# PWR_PoE_PD_1000BASE-T.net
KiCad netlist of a schematic drawn in Altium Designer
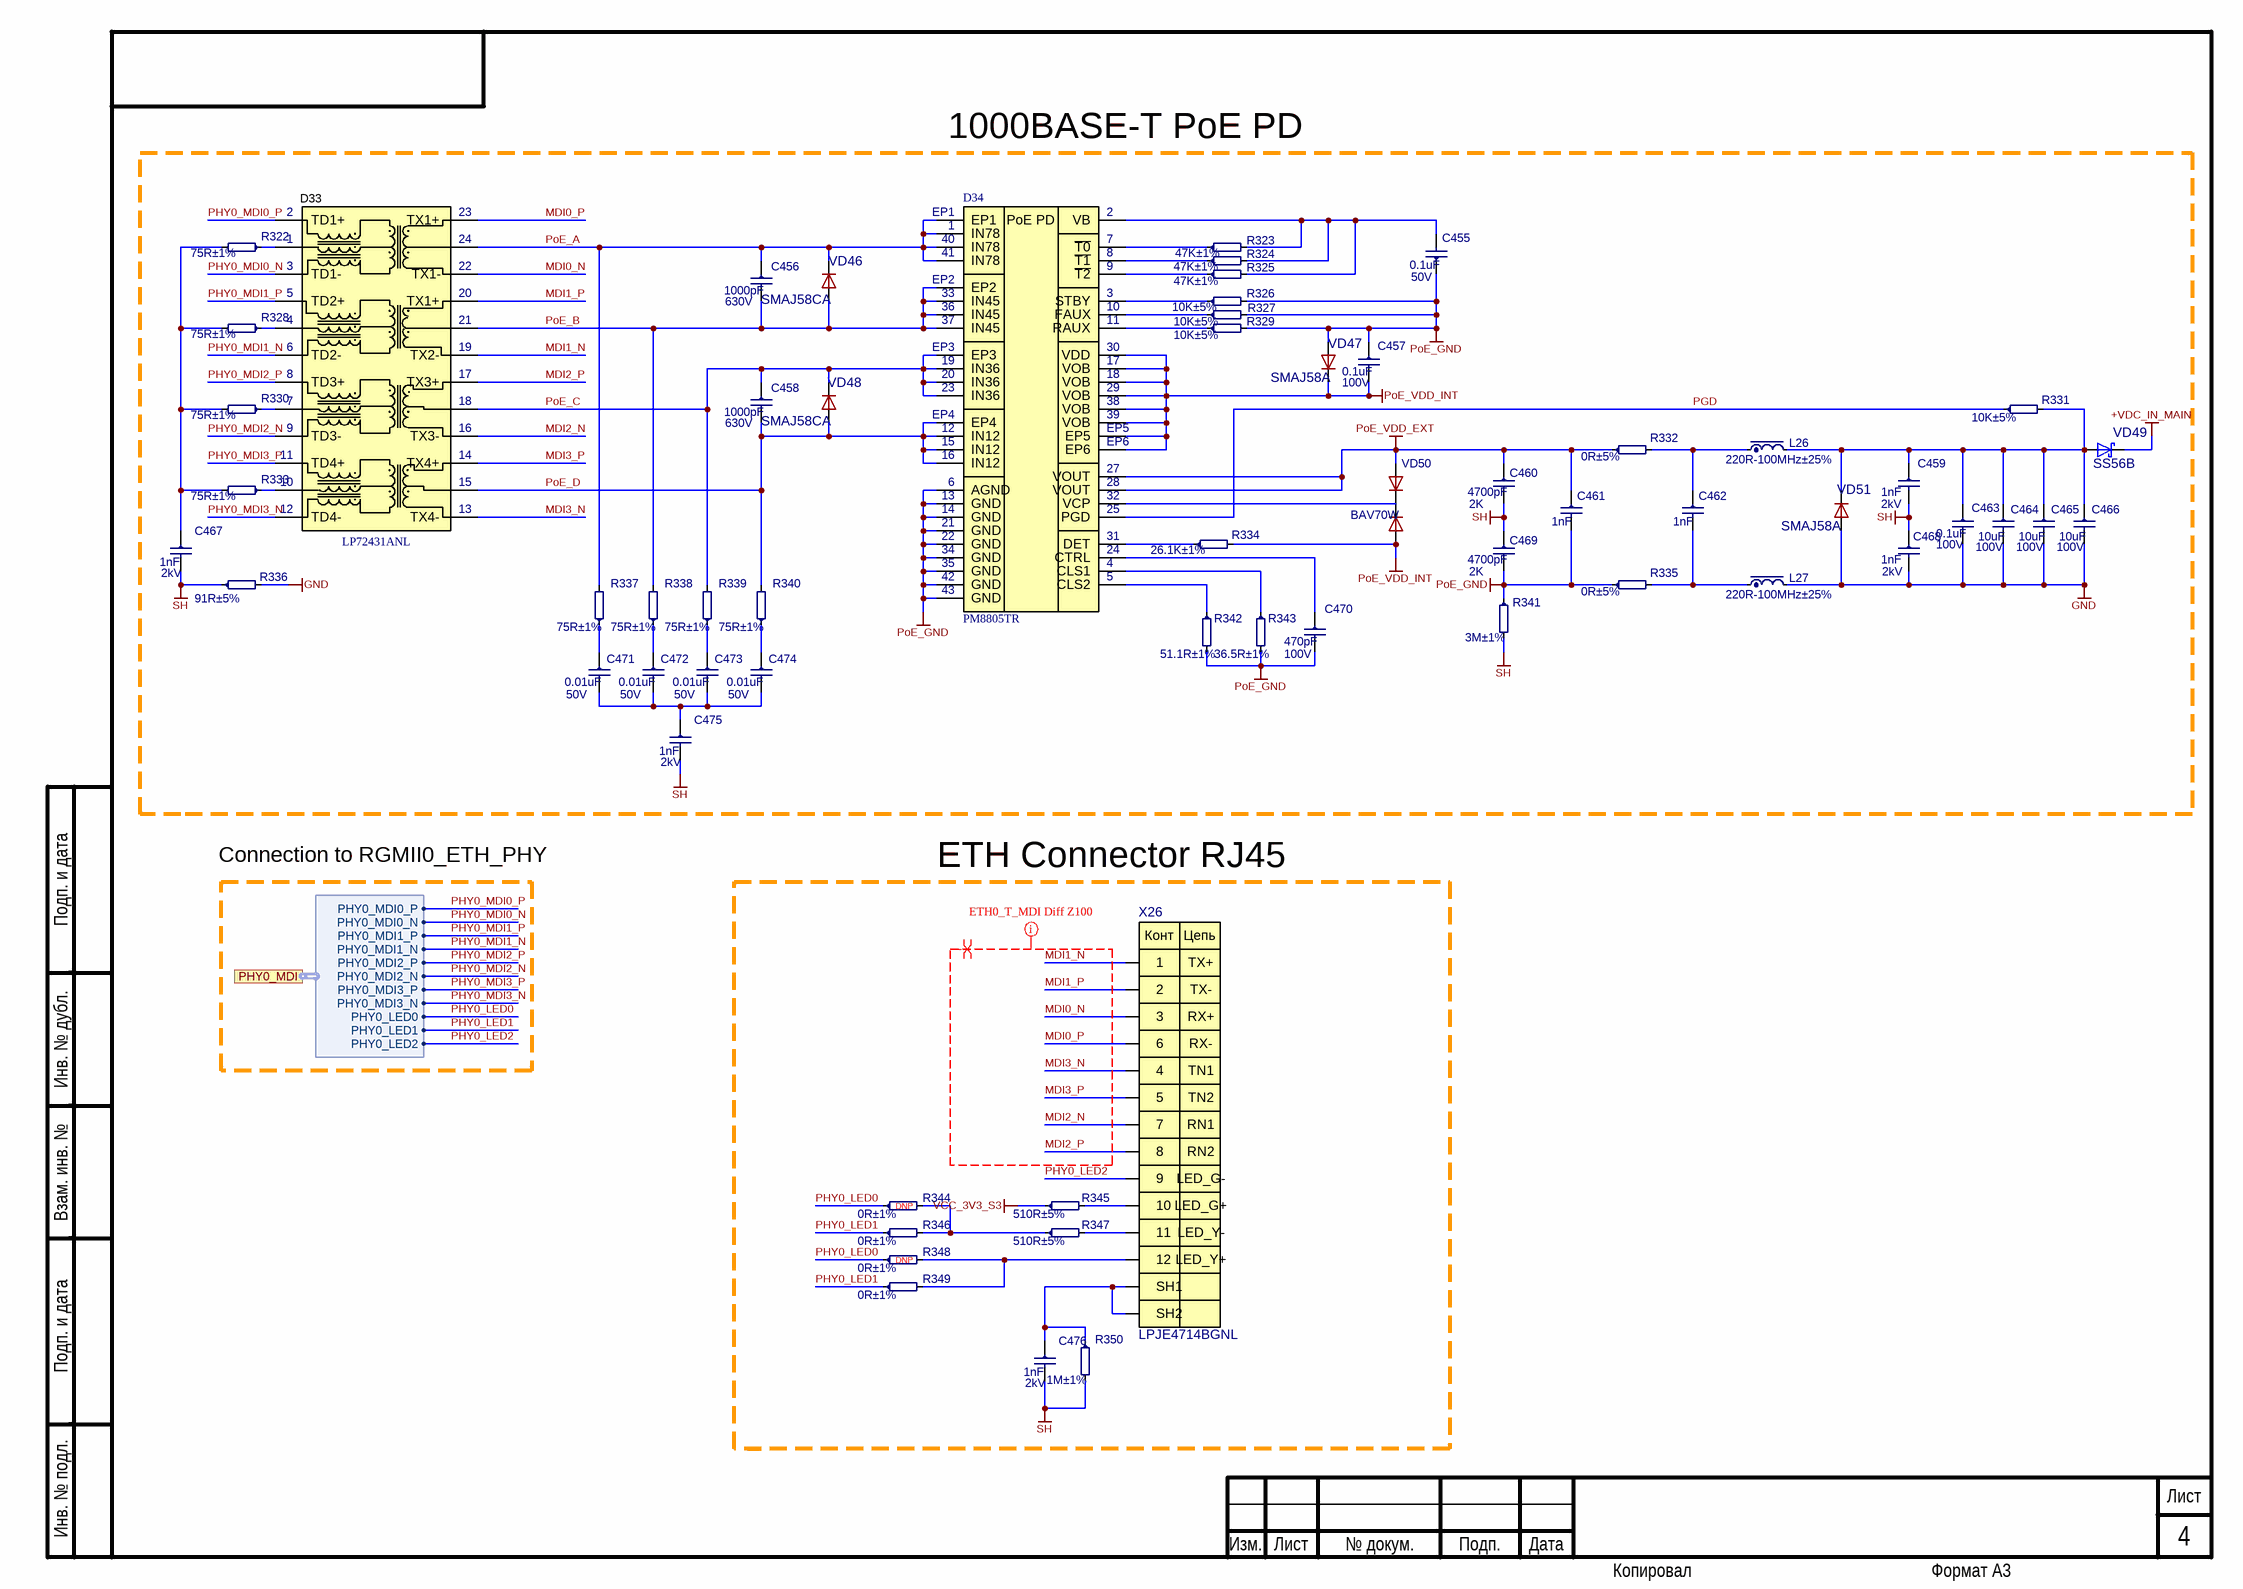
[diagram p0: PWR_PoE_PD_1000BASE-T.SchDoc]

(export (version "E")
  (design (tool "Eeschema 10.0.6"))
  (components
    (comp (ref "C455")
      (value "0.1uF")
      (footprint "C0603")
      (fields
        (field (name "VOLTAGE") "50V")
        (field (name "PART NUMBER") "0603-X7R-50V-0.1uF±10%")
        (field (name "TOLERANCE") "10%")
        (field (name "MANUFACTURER") "Yageo")
      )
      (libsource (lib "ATB") (part "C"))
    )
    (comp (ref "C456")
      (value "1000pF")
      (footprint "C1206")
      (fields
        (field (name "VOLTAGE") "630V")
        (field (name "PART NUMBER") "1206-NP0-630V-1000pF±5%")
        (field (name "TOLERANCE") "5%")
        (field (name "MANUFACTURER") "Yageo")
      )
      (libsource (lib "ATB") (part "C"))
    )
    (comp (ref "C457")
      (value "0.1uF")
      (footprint "C1206")
      (fields
        (field (name "VOLTAGE") "100V")
        (field (name "PART NUMBER") "1206-X7R-100V-0.1uF±10%")
        (field (name "TOLERANCE") "10%")
        (field (name "MANUFACTURER") "KEMET")
      )
      (libsource (lib "ATB") (part "C"))
    )
    (comp (ref "C458")
      (value "1000pF")
      (footprint "C1206")
      (fields
        (field (name "VOLTAGE") "630V")
        (field (name "PART NUMBER") "1206-NP0-630V-1000pF±5%")
        (field (name "TOLERANCE") "5%")
        (field (name "MANUFACTURER") "Yageo")
      )
      (libsource (lib "ATB") (part "C"))
    )
    (comp (ref "C459")
      (value "1nF")
      (footprint "C1812")
      (fields
        (field (name "VOLTAGE") "2kV")
        (field (name "PART NUMBER") "1812-C0G-2kV-1nF±10%")
        (field (name "TOLERANCE") "5%")
        (field (name "MANUFACTURER") "FH")
      )
      (libsource (lib "ATB") (part "C"))
    )
    (comp (ref "C460")
      (value "4700pF")
      (footprint "C1206")
      (fields
        (field (name "VOLTAGE") "2K")
        (field (name "PART NUMBER") "1206-X7R-2K-4700pF±10%")
        (field (name "TOLERANCE") "10%")
        (field (name "MANUFACTURER") "FH")
      )
      (libsource (lib "ATB") (part "C"))
    )
    (comp (ref "C461")
      (value "1nF")
      (footprint "C1206")
      (description "Ceramic Capacitor 1206 1nF ±10% 2kV X7R")
      (fields (field (name "VOLTAGE") "2kV") (field (name "PART NUMBER") "1206-X7R-2K-1000pF±10%"))
      (libsource (lib "ATB") (part "C"))
    )
    (comp (ref "C462")
      (value "1nF")
      (footprint "C1206")
      (description "Ceramic Capacitor 1206 1nF ±10% 2kV X7R")
      (fields (field (name "VOLTAGE") "2kV") (field (name "PART NUMBER") "1206-X7R-2K-1000pF±10%"))
      (libsource (lib "ATB") (part "C"))
    )
    (comp (ref "C463")
      (value "0.1uF")
      (footprint "C1206")
      (fields
        (field (name "VOLTAGE") "100V")
        (field (name "PART NUMBER") "1206-X7R-100V-0.1uF±10%")
        (field (name "TOLERANCE") "10%")
        (field (name "MANUFACTURER") "KEMET")
      )
      (libsource (lib "ATB") (part "C"))
    )
    (comp (ref "C464")
      (value "10uF")
      (footprint "C1210")
      (fields
        (field (name "VOLTAGE") "100V")
        (field (name "PART NUMBER") "1210-X7S-100V-10uF±10%")
        (field (name "TOLERANCE") "10%")
        (field (name "MANUFACTURER") "Samsung Electro-Mechanics")
      )
      (libsource (lib "ATB") (part "C"))
    )
    (comp (ref "C465")
      (value "10uF")
      (footprint "C1210")
      (fields
        (field (name "VOLTAGE") "100V")
        (field (name "PART NUMBER") "1210-X7S-100V-10uF±10%")
        (field (name "TOLERANCE") "10%")
        (field (name "MANUFACTURER") "Samsung Electro-Mechanics")
      )
      (libsource (lib "ATB") (part "C"))
    )
    (comp (ref "C466")
      (value "10uF")
      (footprint "C1210")
      (fields
        (field (name "VOLTAGE") "100V")
        (field (name "PART NUMBER") "1210-X7S-100V-10uF±10%")
        (field (name "TOLERANCE") "10%")
        (field (name "MANUFACTURER") "Samsung Electro-Mechanics")
      )
      (libsource (lib "ATB") (part "C"))
    )
    (comp (ref "C467")
      (value "1nF")
      (footprint "C1812")
      (fields
        (field (name "VOLTAGE") "2kV")
        (field (name "PART NUMBER") "1812-C0G-2kV-1nF±10%")
        (field (name "TOLERANCE") "5%")
        (field (name "MANUFACTURER") "FH")
      )
      (libsource (lib "ATB") (part "C"))
    )
    (comp (ref "C468")
      (value "1nF")
      (footprint "C1812")
      (fields
        (field (name "VOLTAGE") "2kV")
        (field (name "PART NUMBER") "1812-C0G-2kV-1nF±10%")
        (field (name "TOLERANCE") "5%")
        (field (name "MANUFACTURER") "FH")
      )
      (libsource (lib "ATB") (part "C"))
    )
    (comp (ref "C469")
      (value "4700pF")
      (footprint "C1206")
      (fields
        (field (name "VOLTAGE") "2K")
        (field (name "PART NUMBER") "1206-X7R-2K-4700pF±10%")
        (field (name "TOLERANCE") "10%")
        (field (name "MANUFACTURER") "FH")
      )
      (libsource (lib "ATB") (part "C"))
    )
    (comp (ref "C470")
      (value "470pF")
      (footprint "C0805")
      (fields
        (field (name "VOLTAGE") "100V")
        (field (name "PART NUMBER") "0805-X7R-100V-470pF±10%")
        (field (name "TOLERANCE") "10%")
        (field (name "MANUFACTURER") "Yageo")
      )
      (libsource (lib "ATB") (part "C"))
    )
    (comp (ref "C471")
      (value "0.01uF")
      (footprint "C0603")
      (fields
        (field (name "VOLTAGE") "50V")
        (field (name "PART NUMBER") "0603-X7R-50V-0.01uF±10%")
        (field (name "TOLERANCE") "10%")
        (field (name "MANUFACTURER") "Yageo")
      )
      (libsource (lib "ATB") (part "C"))
    )
    (comp (ref "C472")
      (value "0.01uF")
      (footprint "C0603")
      (fields
        (field (name "VOLTAGE") "50V")
        (field (name "PART NUMBER") "0603-X7R-50V-0.01uF±10%")
        (field (name "TOLERANCE") "10%")
        (field (name "MANUFACTURER") "Yageo")
      )
      (libsource (lib "ATB") (part "C"))
    )
    (comp (ref "C473")
      (value "0.01uF")
      (footprint "C0603")
      (fields
        (field (name "VOLTAGE") "50V")
        (field (name "PART NUMBER") "0603-X7R-50V-0.01uF±10%")
        (field (name "TOLERANCE") "10%")
        (field (name "MANUFACTURER") "Yageo")
      )
      (libsource (lib "ATB") (part "C"))
    )
    (comp (ref "C474")
      (value "0.01uF")
      (footprint "C0603")
      (fields
        (field (name "VOLTAGE") "50V")
        (field (name "PART NUMBER") "0603-X7R-50V-0.01uF±10%")
        (field (name "TOLERANCE") "10%")
        (field (name "MANUFACTURER") "Yageo")
      )
      (libsource (lib "ATB") (part "C"))
    )
    (comp (ref "C475")
      (value "1nF")
      (footprint "C1812")
      (fields
        (field (name "VOLTAGE") "2kV")
        (field (name "PART NUMBER") "1812-C0G-2kV-1nF±10%")
        (field (name "TOLERANCE") "5%")
        (field (name "MANUFACTURER") "FH")
      )
      (libsource (lib "ATB") (part "C"))
    )
    (comp (ref "C476")
      (value "1nF")
      (footprint "C1812")
      (fields
        (field (name "VOLTAGE") "2kV")
        (field (name "PART NUMBER") "1812-C0G-2kV-1nF±10%")
        (field (name "TOLERANCE") "5%")
        (field (name "MANUFACTURER") "FH")
      )
      (libsource (lib "ATB") (part "C"))
    )
    (comp (ref "D33")
      (value "LP72431ANL")
      (footprint "LP72431ANL")
      (fields (field (name "MANUFACTURER") "LINK-PP"))
      (libsource (lib "LIB_RK") (part "LP72431ANL"))
    )
    (comp (ref "D34")
      (value "PM8805TR")
      (footprint "PM8805TR")
      (fields (field (name "MANUFACTURER") "ST"))
      (libsource (lib "LIB_RK") (part "PM8805TR"))
    )
    (comp (ref "L26")
      (value "220R-100MHz±25%")
      (footprint "L0805")
      (fields
        (field (name "PART NUMBER") "0805-3A-220R-100MHz")
        (field (name "TOLERANCE") "25%")
        (field (name "MANUFACTURER") "TDK")
      )
      (libsource (lib "ATB") (part "L"))
    )
    (comp (ref "L27")
      (value "220R-100MHz±25%")
      (footprint "L0805")
      (fields
        (field (name "PART NUMBER") "0805-3A-220R-100MHz")
        (field (name "TOLERANCE") "25%")
        (field (name "MANUFACTURER") "TDK")
      )
      (libsource (lib "ATB") (part "L"))
    )
    (comp (ref "R322")
      (value "75R±1%")
      (footprint "R0603")
      (fields
        (field (name "PART NUMBER") "0603-0.1W-75R-100ppm±1%")
        (field (name "TOLERANCE") "1%")
        (field (name "MANUFACTURER") "Yageo")
      )
      (libsource (lib "ATB") (part "R"))
    )
    (comp (ref "R323")
      (value "47K±1%")
      (footprint "R0402")
      (fields
        (field (name "PART NUMBER") "0402-0.0625W-47K-100ppm±1%")
        (field (name "TOLERANCE") "1%")
        (field (name "MANUFACTURER") "Yageo")
      )
      (libsource (lib "ATB") (part "R"))
    )
    (comp (ref "R324")
      (value "47K±1%")
      (footprint "R0402")
      (fields
        (field (name "PART NUMBER") "0402-0.0625W-47K-100ppm±1%")
        (field (name "TOLERANCE") "1%")
        (field (name "MANUFACTURER") "Yageo")
      )
      (libsource (lib "ATB") (part "R"))
    )
    (comp (ref "R325")
      (value "47K±1%")
      (footprint "R0402")
      (fields
        (field (name "PART NUMBER") "0402-0.0625W-47K-100ppm±1%")
        (field (name "TOLERANCE") "1%")
        (field (name "MANUFACTURER") "Yageo")
      )
      (libsource (lib "ATB") (part "R"))
    )
    (comp (ref "R326")
      (value "10K±5%")
      (footprint "R0402")
      (fields
        (field (name "PART NUMBER") "0402-0.0625W-10K-100ppm±5%")
        (field (name "TOLERANCE") "5%")
        (field (name "MANUFACTURER") "Yageo")
      )
      (libsource (lib "ATB") (part "R"))
    )
    (comp (ref "R327")
      (value "10K±5%")
      (footprint "R0402")
      (fields
        (field (name "PART NUMBER") "0402-0.0625W-10K-100ppm±5%")
        (field (name "TOLERANCE") "5%")
        (field (name "MANUFACTURER") "Yageo")
      )
      (libsource (lib "ATB") (part "R"))
    )
    (comp (ref "R328")
      (value "75R±1%")
      (footprint "R0603")
      (fields
        (field (name "PART NUMBER") "0603-0.1W-75R-100ppm±1%")
        (field (name "TOLERANCE") "1%")
        (field (name "MANUFACTURER") "Yageo")
      )
      (libsource (lib "ATB") (part "R"))
    )
    (comp (ref "R329")
      (value "10K±5%")
      (footprint "R0402")
      (fields
        (field (name "PART NUMBER") "0402-0.0625W-10K-100ppm±5%")
        (field (name "TOLERANCE") "5%")
        (field (name "MANUFACTURER") "Yageo")
      )
      (libsource (lib "ATB") (part "R"))
    )
    (comp (ref "R330")
      (value "75R±1%")
      (footprint "R0603")
      (fields
        (field (name "PART NUMBER") "0603-0.1W-75R-100ppm±1%")
        (field (name "TOLERANCE") "1%")
        (field (name "MANUFACTURER") "Yageo")
      )
      (libsource (lib "ATB") (part "R"))
    )
    (comp (ref "R331")
      (value "10K±5%")
      (footprint "R1206")
      (fields
        (field (name "PART NUMBER") "1206-0.25W-10K-100ppm±5%")
        (field (name "TOLERANCE") "5%")
        (field (name "MANUFACTURER") "Yageo")
      )
      (libsource (lib "ATB") (part "R"))
    )
    (comp (ref "R332")
      (value "0R±5%")
      (footprint "R1206")
      (fields
        (field (name "PART NUMBER") "1206-0.25W-0R-200ppm±5%")
        (field (name "TOLERANCE") "5%")
        (field (name "MANUFACTURER") "Yageo")
      )
      (libsource (lib "ATB") (part "R"))
    )
    (comp (ref "R333")
      (value "75R±1%")
      (footprint "R0603")
      (fields
        (field (name "PART NUMBER") "0603-0.1W-75R-100ppm±1%")
        (field (name "TOLERANCE") "1%")
        (field (name "MANUFACTURER") "Yageo")
      )
      (libsource (lib "ATB") (part "R"))
    )
    (comp (ref "R334")
      (value "26.1K±1%")
      (footprint "R0603")
      (fields
        (field (name "PART NUMBER") "0603-0.1W-26.1K-100ppm±1%")
        (field (name "TOLERANCE") "1%")
        (field (name "MANUFACTURER") "NIC Components Corp.")
      )
      (libsource (lib "ATB") (part "R"))
    )
    (comp (ref "R335")
      (value "0R±5%")
      (footprint "R1206")
      (fields
        (field (name "PART NUMBER") "1206-0.25W-0R-200ppm±5%")
        (field (name "TOLERANCE") "5%")
        (field (name "MANUFACTURER") "Yageo")
      )
      (libsource (lib "ATB") (part "R"))
    )
    (comp (ref "R336")
      (value "91R±5%")
      (footprint "R2010")
      (description "Chip Resistor 2010 0Ω ±5% 200V ±200ppm/℃ Thick Film")
      (fields (field (name "PART NUMBER") "2010-0.75W-91R-200ppm±5%") (field (name "TOLERANCE") "5%"))
      (libsource (lib "ATB") (part "R"))
    )
    (comp (ref "R337")
      (value "75R±1%")
      (footprint "R0603")
      (fields
        (field (name "PART NUMBER") "0603-0.1W-75R-100ppm±1%")
        (field (name "TOLERANCE") "1%")
        (field (name "MANUFACTURER") "Yageo")
      )
      (libsource (lib "ATB") (part "R"))
    )
    (comp (ref "R338")
      (value "75R±1%")
      (footprint "R0603")
      (fields
        (field (name "PART NUMBER") "0603-0.1W-75R-100ppm±1%")
        (field (name "TOLERANCE") "1%")
        (field (name "MANUFACTURER") "Yageo")
      )
      (libsource (lib "ATB") (part "R"))
    )
    (comp (ref "R339")
      (value "75R±1%")
      (footprint "R0603")
      (fields
        (field (name "PART NUMBER") "0603-0.1W-75R-100ppm±1%")
        (field (name "TOLERANCE") "1%")
        (field (name "MANUFACTURER") "Yageo")
      )
      (libsource (lib "ATB") (part "R"))
    )
    (comp (ref "R340")
      (value "75R±1%")
      (footprint "R0603")
      (fields
        (field (name "PART NUMBER") "0603-0.1W-75R-100ppm±1%")
        (field (name "TOLERANCE") "1%")
        (field (name "MANUFACTURER") "Yageo")
      )
      (libsource (lib "ATB") (part "R"))
    )
    (comp (ref "R341")
      (value "3M±1%")
      (footprint "R1206")
      (description "Chip Resistor 1206 3MΩ ±1% 200V ±100ppm/℃ Thick Film")
      (fields (field (name "PART NUMBER") "1206-0.25W-3M-100ppm±1%") (field (name "TOLERANCE") "1%"))
      (libsource (lib "ATB") (part "R"))
    )
    (comp (ref "R342")
      (value "51.1R±1%")
      (footprint "R0805")
      (description "Chip Resistor 0805 200Ω ±1% 150V ±100ppm/℃ Thick Film")
      (fields (field (name "PART NUMBER") "0805-0.125W-51.1R-100ppm±1%") (field (name "TOLERANCE") "1%"))
      (libsource (lib "ATB") (part "R"))
    )
    (comp (ref "R343")
      (value "36.5R±1%")
      (footprint "R0805")
      (description "Chip Resistor 0805 200Ω ±1% 150V ±100ppm/℃ Thick Film")
      (fields (field (name "PART NUMBER") "0805-0.125W-36.5R-100ppm±1%") (field (name "TOLERANCE") "1%"))
      (libsource (lib "ATB") (part "R"))
    )
    (comp (ref "R344")
      (value "0R±1%")
      (footprint "R0402")
      (description "Chip Resistor 0402 0Ω ±1% 50V ±100ppm/℃ Thick Film")
      (fields (field (name "PART NUMBER") "0402-0.0625W-0R-100ppm±1%") (field (name "TOLERANCE") "1%"))
      (libsource (lib "ATB") (part "R"))
    )
    (comp (ref "R345")
      (value "510R±5%")
      (footprint "R0402")
      (fields
        (field (name "PART NUMBER") "0402-0.0625W-510R-100ppm±5%")
        (field (name "TOLERANCE") "5%")
        (field (name "MANUFACTURER") "Yageo")
      )
      (libsource (lib "ATB") (part "R"))
    )
    (comp (ref "R346")
      (value "0R±1%")
      (footprint "R0402")
      (description "Chip Resistor 0402 0Ω ±1% 50V ±100ppm/℃ Thick Film")
      (fields (field (name "PART NUMBER") "0402-0.0625W-0R-100ppm±1%") (field (name "TOLERANCE") "1%"))
      (libsource (lib "ATB") (part "R"))
    )
    (comp (ref "R347")
      (value "510R±5%")
      (footprint "R0402")
      (fields
        (field (name "PART NUMBER") "0402-0.0625W-510R-100ppm±5%")
        (field (name "TOLERANCE") "5%")
        (field (name "MANUFACTURER") "Yageo")
      )
      (libsource (lib "ATB") (part "R"))
    )
    (comp (ref "R348")
      (value "0R±1%")
      (footprint "R0402")
      (description "Chip Resistor 0402 0Ω ±1% 50V ±100ppm/℃ Thick Film")
      (fields (field (name "PART NUMBER") "0402-0.0625W-0R-100ppm±1%") (field (name "TOLERANCE") "1%"))
      (libsource (lib "ATB") (part "R"))
    )
    (comp (ref "R349")
      (value "0R±1%")
      (footprint "R0402")
      (description "Chip Resistor 0402 0Ω ±1% 50V ±100ppm/℃ Thick Film")
      (fields (field (name "PART NUMBER") "0402-0.0625W-0R-100ppm±1%") (field (name "TOLERANCE") "1%"))
      (libsource (lib "ATB") (part "R"))
    )
    (comp (ref "R350")
      (value "1M±1%")
      (footprint "R1206")
      (description "Chip Resistor 1206 1MΩ ±1% 200V ±100ppm/℃ Thick Film")
      (fields (field (name "PART NUMBER") "1206-0.25W-1M-100ppm±1%") (field (name "TOLERANCE") "1%"))
      (libsource (lib "ATB") (part "R"))
    )
    (comp (ref "VD46")
      (value "SMAJ58CA")
      (footprint "DO-214AC")
      (description "surface mount 500 W Transient Voltage Suppressor")
      (fields (field (name "MANUFACTURER") "Littelfuse"))
      (libsource (lib "ATB") (part "Diod"))
    )
    (comp (ref "VD47")
      (value "SMAJ58A")
      (footprint "DO-214AC")
      (description "surface mount 500 W Transient Voltage Suppressor")
      (fields (field (name "MANUFACTURER") "Littelfuse"))
      (libsource (lib "ATB") (part "Diod"))
    )
    (comp (ref "VD48")
      (value "SMAJ58CA")
      (footprint "DO-214AC")
      (description "surface mount 500 W Transient Voltage Suppressor")
      (fields (field (name "MANUFACTURER") "Littelfuse"))
      (libsource (lib "ATB") (part "Diod"))
    )
    (comp (ref "VD49")
      (value "SS56B")
      (footprint "DO-214AA")
      (description "Schottky Rectifier")
      (fields (field (name "MANUFACTURER") "Yangjie (YJ)"))
      (libsource (lib "ATB") (part "Shotki"))
    )
    (comp (ref "VD50")
      (value "BAV70W")
      (footprint "SOT323")
      (description "70V Dual Common Cathode 1V 6ns 200mA SOT-323 Switching Diode")
      (fields (field (name "MANUFACTURER") "LRC"))
      (libsource (lib "ATB") (part "Diode-3P-AAC"))
    )
    (comp (ref "VD51")
      (value "SMAJ58A")
      (footprint "DO-214AC")
      (description "surface mount 500 W Transient Voltage Suppressor")
      (fields (field (name "MANUFACTURER") "Littelfuse"))
      (libsource (lib "ATB") (part "Diod"))
    )
    (comp (ref "X26")
      (value "LPJE4714BGNL")
      (footprint "LPJE4714BGNL")
      (fields (field (name "MANUFACTURER") "LINK-PP"))
      (libsource (lib "LIB_RK") (part "LPJE4714BGNL"))
    )
  )
  (nets
    (net (code "2") (name "+VDC_IN_MAIN") (class "Default")
      (node (ref "VD49") (pin "1") (pinfunction "K_1") (pintype "passive"))
    )
    (net (code "3") (name "/MDI0_N") (class "Default")
      (node (ref "D33") (pin "22") (pinfunction "TX1-_22") (pintype "passive"))
      (node (ref "X26") (pin "3") (pinfunction "3_3") (pintype "passive"))
    )
    (net (code "4") (name "/MDI0_P") (class "Default")
      (node (ref "D33") (pin "23") (pinfunction "TX1+_23") (pintype "passive"))
      (node (ref "X26") (pin "6") (pinfunction "6_6") (pintype "passive"))
    )
    (net (code "5") (name "/MDI1_N") (class "Default")
      (node (ref "D33") (pin "19") (pinfunction "TX2-_19") (pintype "passive"))
      (node (ref "X26") (pin "1") (pinfunction "1_1") (pintype "passive"))
    )
    (net (code "6") (name "/MDI1_P") (class "Default")
      (node (ref "D33") (pin "20") (pinfunction "TX1+_20") (pintype "passive"))
      (node (ref "X26") (pin "2") (pinfunction "2_2") (pintype "passive"))
    )
    (net (code "7") (name "/MDI2_N") (class "Default")
      (node (ref "D33") (pin "16") (pinfunction "TX3-_16") (pintype "passive"))
      (node (ref "X26") (pin "7") (pinfunction "7_7") (pintype "passive"))
    )
    (net (code "8") (name "/MDI2_P") (class "Default")
      (node (ref "D33") (pin "17") (pinfunction "TX3+_17") (pintype "passive"))
      (node (ref "X26") (pin "8") (pinfunction "8_8") (pintype "passive"))
    )
    (net (code "9") (name "/MDI3_N") (class "Default")
      (node (ref "D33") (pin "13") (pinfunction "TX4-_13") (pintype "passive"))
      (node (ref "X26") (pin "4") (pinfunction "4_4") (pintype "passive"))
    )
    (net (code "10") (name "/MDI3_P") (class "Default")
      (node (ref "D33") (pin "14") (pinfunction "TX4+_14") (pintype "passive"))
      (node (ref "X26") (pin "5") (pinfunction "5_5") (pintype "passive"))
    )
    (net (code "11") (name "/PGD") (class "Default")
      (node (ref "D34") (pin "25") (pinfunction "PGD_25") (pintype "passive"))
      (node (ref "R331") (pin "1") (pinfunction "1_1") (pintype "passive"))
    )
    (net (code "12") (name "/PHY0_LED0") (class "Default")
      (node (ref "R344") (pin "1") (pinfunction "1_1") (pintype "passive"))
      (node (ref "R348") (pin "1") (pinfunction "1_1") (pintype "passive"))
    )
    (net (code "13") (name "/PHY0_LED1") (class "Default")
      (node (ref "R346") (pin "1") (pinfunction "1_1") (pintype "passive"))
      (node (ref "R349") (pin "1") (pinfunction "1_1") (pintype "passive"))
    )
    (net (code "14") (name "/PHY0_LED2") (class "Default")
      (node (ref "X26") (pin "9") (pinfunction "9_9") (pintype "passive"))
    )
    (net (code "15") (name "/PHY0_MDI0_N") (class "Default")
      (node (ref "D33") (pin "3") (pinfunction "TD1-_3") (pintype "passive"))
    )
    (net (code "16") (name "/PHY0_MDI0_P") (class "Default")
      (node (ref "D33") (pin "2") (pinfunction "TD1+_2") (pintype "passive"))
    )
    (net (code "17") (name "/PHY0_MDI1_N") (class "Default")
      (node (ref "D33") (pin "6") (pinfunction "TD2-_6") (pintype "passive"))
    )
    (net (code "18") (name "/PHY0_MDI1_P") (class "Default")
      (node (ref "D33") (pin "5") (pinfunction "TD2+_5") (pintype "passive"))
    )
    (net (code "19") (name "/PHY0_MDI2_N") (class "Default")
      (node (ref "D33") (pin "9") (pinfunction "TD3-_9") (pintype "passive"))
    )
    (net (code "20") (name "/PHY0_MDI2_P") (class "Default")
      (node (ref "D33") (pin "8") (pinfunction "TD3+_8") (pintype "passive"))
    )
    (net (code "21") (name "/PHY0_MDI3_N") (class "Default")
      (node (ref "D33") (pin "12") (pinfunction "TD4-_12") (pintype "passive"))
    )
    (net (code "22") (name "/PHY0_MDI3_P") (class "Default")
      (node (ref "D33") (pin "11") (pinfunction "TD4+_11") (pintype "passive"))
    )
    (net (code "23") (name "/PoE_A") (class "Default")
      (node (ref "C456") (pin "1") (pinfunction "1_1") (pintype "passive"))
      (node (ref "D33") (pin "24") (pinfunction "TCT_1_24") (pintype "passive"))
      (node (ref "D34") (pin "1") (pinfunction "IN78_1") (pintype "passive"))
      (node (ref "D34") (pin "40") (pinfunction "IN78_40") (pintype "passive"))
      (node (ref "D34") (pin "41") (pinfunction "IN78_41") (pintype "passive"))
      (node (ref "D34") (pin "EP1") (pinfunction "EP1_EP1") (pintype "passive"))
      (node (ref "R337") (pin "2") (pinfunction "2_2") (pintype "passive"))
      (node (ref "VD46") (pin "1") (pinfunction "C_1") (pintype "passive"))
    )
    (net (code "24") (name "/PoE_B") (class "Default")
      (node (ref "C456") (pin "2") (pinfunction "2_2") (pintype "passive"))
      (node (ref "D33") (pin "21") (pinfunction "TCT_2_21") (pintype "passive"))
      (node (ref "D34") (pin "33") (pinfunction "IN45_33") (pintype "passive"))
      (node (ref "D34") (pin "36") (pinfunction "IN45_36") (pintype "passive"))
      (node (ref "D34") (pin "37") (pinfunction "IN45_37") (pintype "passive"))
      (node (ref "D34") (pin "EP2") (pinfunction "EP2_EP2") (pintype "passive"))
      (node (ref "R338") (pin "2") (pinfunction "2_2") (pintype "passive"))
      (node (ref "VD46") (pin "2") (pinfunction "A_2") (pintype "passive"))
    )
    (net (code "25") (name "/PoE_C") (class "Default")
      (node (ref "C458") (pin "1") (pinfunction "1_1") (pintype "passive"))
      (node (ref "D33") (pin "18") (pinfunction "TCT_3_18") (pintype "passive"))
      (node (ref "D34") (pin "19") (pinfunction "IN36_19") (pintype "passive"))
      (node (ref "D34") (pin "20") (pinfunction "IN36_20") (pintype "passive"))
      (node (ref "D34") (pin "23") (pinfunction "IN36_23") (pintype "passive"))
      (node (ref "D34") (pin "EP3") (pinfunction "EP3_EP3") (pintype "passive"))
      (node (ref "R339") (pin "2") (pinfunction "2_2") (pintype "passive"))
      (node (ref "VD48") (pin "1") (pinfunction "C_1") (pintype "passive"))
    )
    (net (code "26") (name "/PoE_D") (class "Default")
      (node (ref "C458") (pin "2") (pinfunction "2_2") (pintype "passive"))
      (node (ref "D33") (pin "15") (pinfunction "TCT_4_15") (pintype "passive"))
      (node (ref "D34") (pin "12") (pinfunction "IN12_12") (pintype "passive"))
      (node (ref "D34") (pin "15") (pinfunction "IN12_15") (pintype "passive"))
      (node (ref "D34") (pin "16") (pinfunction "IN12_16") (pintype "passive"))
      (node (ref "D34") (pin "EP4") (pinfunction "EP4_EP4") (pintype "passive"))
      (node (ref "R340") (pin "2") (pinfunction "2_2") (pintype "passive"))
      (node (ref "VD48") (pin "2") (pinfunction "A_2") (pintype "passive"))
    )
    (net (code "28") (name "GND") (class "Default")
      (node (ref "C463") (pin "2") (pinfunction "2_2") (pintype "passive"))
      (node (ref "C464") (pin "2") (pinfunction "2_2") (pintype "passive"))
      (node (ref "C465") (pin "2") (pinfunction "2_2") (pintype "passive"))
      (node (ref "C466") (pin "2") (pinfunction "2_2") (pintype "passive"))
      (node (ref "C468") (pin "2") (pinfunction "2_2") (pintype "passive"))
      (node (ref "L27") (pin "2") (pinfunction "2_2") (pintype "passive"))
      (node (ref "R336") (pin "2") (pinfunction "2_2") (pintype "passive"))
      (node (ref "VD51") (pin "2") (pinfunction "A_2") (pintype "passive"))
    )
    (net (code "29") (name "Net-(C462-Pad1)") (class "Default")
      (node (ref "C462") (pin "1") (pinfunction "1_1") (pintype "passive"))
      (node (ref "L26") (pin "1") (pinfunction "1_1") (pintype "passive"))
      (node (ref "R332") (pin "2") (pinfunction "2_2") (pintype "passive"))
    )
    (net (code "30") (name "Net-(C462-Pad2)") (class "Default")
      (node (ref "C462") (pin "2") (pinfunction "2_2") (pintype "passive"))
      (node (ref "L27") (pin "1") (pinfunction "1_1") (pintype "passive"))
      (node (ref "R335") (pin "2") (pinfunction "2_2") (pintype "passive"))
    )
    (net (code "31") (name "Net-(C467-Pad1)") (class "Default")
      (node (ref "C467") (pin "1") (pinfunction "1_1") (pintype "passive"))
      (node (ref "R322") (pin "2") (pinfunction "2_2") (pintype "passive"))
      (node (ref "R328") (pin "2") (pinfunction "2_2") (pintype "passive"))
      (node (ref "R330") (pin "2") (pinfunction "2_2") (pintype "passive"))
      (node (ref "R333") (pin "2") (pinfunction "2_2") (pintype "passive"))
    )
    (net (code "32") (name "Net-(C471-Pad1)") (class "Default")
      (node (ref "C471") (pin "1") (pinfunction "1_1") (pintype "passive"))
      (node (ref "R337") (pin "1") (pinfunction "1_1") (pintype "passive"))
    )
    (net (code "33") (name "Net-(C471-Pad2)") (class "Default")
      (node (ref "C471") (pin "2") (pinfunction "2_2") (pintype "passive"))
      (node (ref "C472") (pin "2") (pinfunction "2_2") (pintype "passive"))
      (node (ref "C473") (pin "2") (pinfunction "2_2") (pintype "passive"))
      (node (ref "C474") (pin "2") (pinfunction "2_2") (pintype "passive"))
      (node (ref "C475") (pin "1") (pinfunction "1_1") (pintype "passive"))
    )
    (net (code "34") (name "Net-(C472-Pad1)") (class "Default")
      (node (ref "C472") (pin "1") (pinfunction "1_1") (pintype "passive"))
      (node (ref "R338") (pin "1") (pinfunction "1_1") (pintype "passive"))
    )
    (net (code "35") (name "Net-(C473-Pad1)") (class "Default")
      (node (ref "C473") (pin "1") (pinfunction "1_1") (pintype "passive"))
      (node (ref "R339") (pin "1") (pinfunction "1_1") (pintype "passive"))
    )
    (net (code "36") (name "Net-(C474-Pad1)") (class "Default")
      (node (ref "C474") (pin "1") (pinfunction "1_1") (pintype "passive"))
      (node (ref "R340") (pin "1") (pinfunction "1_1") (pintype "passive"))
    )
    (net (code "37") (name "Net-(C476-Pad1)") (class "Default")
      (node (ref "C476") (pin "1") (pinfunction "1_1") (pintype "passive"))
      (node (ref "R350") (pin "1") (pinfunction "1_1") (pintype "passive"))
      (node (ref "X26") (pin "SH1") (pinfunction "SH1_SH1") (pintype "passive"))
      (node (ref "X26") (pin "SH2") (pinfunction "SH2_SH2") (pintype "passive"))
    )
    (net (code "38") (name "Net-(D33-TCT1)") (class "Default")
      (node (ref "D33") (pin "1") (pinfunction "TCT1_1") (pintype "passive"))
      (node (ref "R322") (pin "1") (pinfunction "1_1") (pintype "passive"))
    )
    (net (code "39") (name "Net-(D33-TCT2)") (class "Default")
      (node (ref "D33") (pin "4") (pinfunction "TCT2_4") (pintype "passive"))
      (node (ref "R328") (pin "1") (pinfunction "1_1") (pintype "passive"))
    )
    (net (code "40") (name "Net-(D33-TCT3)") (class "Default")
      (node (ref "D33") (pin "7") (pinfunction "TCT3_7") (pintype "passive"))
      (node (ref "R330") (pin "1") (pinfunction "1_1") (pintype "passive"))
    )
    (net (code "41") (name "Net-(D33-TCT4)") (class "Default")
      (node (ref "D33") (pin "10") (pinfunction "TCT4_10") (pintype "passive"))
      (node (ref "R333") (pin "1") (pinfunction "1_1") (pintype "passive"))
    )
    (net (code "42") (name "Net-(D34-CLS1)") (class "Default")
      (node (ref "D34") (pin "4") (pinfunction "CLS1_4") (pintype "passive"))
      (node (ref "R343") (pin "1") (pinfunction "1_1") (pintype "passive"))
    )
    (net (code "43") (name "Net-(D34-CLS2)") (class "Default")
      (node (ref "D34") (pin "5") (pinfunction "CLS2_5") (pintype "passive"))
      (node (ref "R342") (pin "1") (pinfunction "1_1") (pintype "passive"))
    )
    (net (code "44") (name "Net-(D34-CTRL)") (class "Default")
      (node (ref "C470") (pin "1") (pinfunction "1_1") (pintype "passive"))
      (node (ref "D34") (pin "24") (pinfunction "CTRL_24") (pintype "passive"))
    )
    (net (code "45") (name "Net-(D34-DET)") (class "Default")
      (node (ref "D34") (pin "31") (pinfunction "DET_31") (pintype "passive"))
      (node (ref "R334") (pin "1") (pinfunction "1_1") (pintype "passive"))
    )
    (net (code "46") (name "Net-(D34-FAUX)") (class "Default")
      (node (ref "D34") (pin "10") (pinfunction "FAUX_10") (pintype "passive"))
      (node (ref "R327") (pin "1") (pinfunction "1_1") (pintype "passive"))
    )
    (net (code "47") (name "Net-(D34-RAUX)") (class "Default")
      (node (ref "D34") (pin "11") (pinfunction "RAUX_11") (pintype "passive"))
      (node (ref "R329") (pin "1") (pinfunction "1_1") (pintype "passive"))
    )
    (net (code "48") (name "Net-(D34-STBY)") (class "Default")
      (node (ref "D34") (pin "3") (pinfunction "STBY_3") (pintype "passive"))
      (node (ref "R326") (pin "1") (pinfunction "1_1") (pintype "passive"))
    )
    (net (code "49") (name "Net-(D34-VB)") (class "Default")
      (node (ref "C455") (pin "2") (pinfunction "2_2") (pintype "passive"))
      (node (ref "D34") (pin "2") (pinfunction "VB_2") (pintype "passive"))
      (node (ref "R323") (pin "2") (pinfunction "2_2") (pintype "passive"))
      (node (ref "R324") (pin "2") (pinfunction "2_2") (pintype "passive"))
      (node (ref "R325") (pin "2") (pinfunction "2_2") (pintype "passive"))
    )
    (net (code "50") (name "Net-(D34-VCP)") (class "Default")
      (node (ref "D34") (pin "32") (pinfunction "VCP_32") (pintype "passive"))
      (node (ref "VD50") (pin "3") (pinfunction "CC_3") (pintype "passive"))
    )
    (net (code "51") (name "Net-(D34-~{T0})") (class "Default")
      (node (ref "D34") (pin "7") (pinfunction "~{T0}_7") (pintype "passive"))
      (node (ref "R323") (pin "1") (pinfunction "1_1") (pintype "passive"))
    )
    (net (code "52") (name "Net-(D34-~{T1})") (class "Default")
      (node (ref "D34") (pin "8") (pinfunction "~{T1}_8") (pintype "passive"))
      (node (ref "R324") (pin "1") (pinfunction "1_1") (pintype "passive"))
    )
    (net (code "53") (name "Net-(D34-~{T2})") (class "Default")
      (node (ref "D34") (pin "9") (pinfunction "~{T2}_9") (pintype "passive"))
      (node (ref "R325") (pin "1") (pinfunction "1_1") (pintype "passive"))
    )
    (net (code "54") (name "Net-(R344-Pad2)") (class "Default")
      (node (ref "R344") (pin "2") (pinfunction "2_2") (pintype "passive"))
      (node (ref "R346") (pin "2") (pinfunction "2_2") (pintype "passive"))
      (node (ref "R347") (pin "1") (pinfunction "1_1") (pintype "passive"))
    )
    (net (code "55") (name "Net-(R345-Pad2)") (class "Default")
      (node (ref "R345") (pin "2") (pinfunction "2_2") (pintype "passive"))
      (node (ref "X26") (pin "10") (pinfunction "10_10") (pintype "passive"))
    )
    (net (code "56") (name "Net-(R347-Pad2)") (class "Default")
      (node (ref "R347") (pin "2") (pinfunction "2_2") (pintype "passive"))
      (node (ref "X26") (pin "11") (pinfunction "11_11") (pintype "passive"))
    )
    (net (code "57") (name "Net-(R348-Pad2)") (class "Default")
      (node (ref "R348") (pin "2") (pinfunction "2_2") (pintype "passive"))
      (node (ref "R349") (pin "2") (pinfunction "2_2") (pintype "passive"))
      (node (ref "X26") (pin "12") (pinfunction "12_12") (pintype "passive"))
    )
    (net (code "58") (name "Net-(VD49-A)") (class "Default")
      (node (ref "C459") (pin "1") (pinfunction "1_1") (pintype "passive"))
      (node (ref "C463") (pin "1") (pinfunction "1_1") (pintype "passive"))
      (node (ref "C464") (pin "1") (pinfunction "1_1") (pintype "passive"))
      (node (ref "C465") (pin "1") (pinfunction "1_1") (pintype "passive"))
      (node (ref "C466") (pin "1") (pinfunction "1_1") (pintype "passive"))
      (node (ref "L26") (pin "2") (pinfunction "2_2") (pintype "passive"))
      (node (ref "R331") (pin "2") (pinfunction "2_2") (pintype "passive"))
      (node (ref "VD49") (pin "2") (pinfunction "A_2") (pintype "passive"))
      (node (ref "VD51") (pin "1") (pinfunction "C_1") (pintype "passive"))
    )
    (net (code "59") (name "PoE_GND") (class "Default")
      (node (ref "C455") (pin "1") (pinfunction "1_1") (pintype "passive"))
      (node (ref "C457") (pin "1") (pinfunction "1_1") (pintype "passive"))
      (node (ref "C461") (pin "2") (pinfunction "2_2") (pintype "passive"))
      (node (ref "C469") (pin "2") (pinfunction "2_2") (pintype "passive"))
      (node (ref "C470") (pin "2") (pinfunction "2_2") (pintype "passive"))
      (node (ref "D34") (pin "13") (pinfunction "GND_13") (pintype "passive"))
      (node (ref "D34") (pin "14") (pinfunction "GND_14") (pintype "passive"))
      (node (ref "D34") (pin "21") (pinfunction "GND_21") (pintype "passive"))
      (node (ref "D34") (pin "22") (pinfunction "GND_22") (pintype "passive"))
      (node (ref "D34") (pin "34") (pinfunction "GND_34") (pintype "passive"))
      (node (ref "D34") (pin "35") (pinfunction "GND_35") (pintype "passive"))
      (node (ref "D34") (pin "42") (pinfunction "GND_42") (pintype "passive"))
      (node (ref "D34") (pin "43") (pinfunction "GND_43") (pintype "passive"))
      (node (ref "D34") (pin "6") (pinfunction "AGND_6") (pintype "passive"))
      (node (ref "R326") (pin "2") (pinfunction "2_2") (pintype "passive"))
      (node (ref "R327") (pin "2") (pinfunction "2_2") (pintype "passive"))
      (node (ref "R329") (pin "2") (pinfunction "2_2") (pintype "passive"))
      (node (ref "R335") (pin "1") (pinfunction "1_1") (pintype "passive"))
      (node (ref "R341") (pin "1") (pinfunction "1_1") (pintype "passive"))
      (node (ref "R342") (pin "2") (pinfunction "2_2") (pintype "passive"))
      (node (ref "R343") (pin "2") (pinfunction "2_2") (pintype "passive"))
      (node (ref "VD47") (pin "2") (pinfunction "A_2") (pintype "passive"))
    )
    (net (code "60") (name "PoE_VDD_EXT") (class "Default")
      (node (ref "C460") (pin "1") (pinfunction "1_1") (pintype "passive"))
      (node (ref "C461") (pin "1") (pinfunction "1_1") (pintype "passive"))
      (node (ref "D34") (pin "27") (pinfunction "VOUT_27") (pintype "passive"))
      (node (ref "D34") (pin "28") (pinfunction "VOUT_28") (pintype "passive"))
      (node (ref "R332") (pin "1") (pinfunction "1_1") (pintype "passive"))
      (node (ref "VD50") (pin "1") (pinfunction "A_1") (pintype "passive"))
    )
    (net (code "61") (name "PoE_VDD_INT") (class "Default")
      (node (ref "C457") (pin "2") (pinfunction "2_2") (pintype "passive"))
      (node (ref "D34") (pin "17") (pinfunction "VOB_17") (pintype "passive"))
      (node (ref "D34") (pin "18") (pinfunction "VOB_18") (pintype "passive"))
      (node (ref "D34") (pin "29") (pinfunction "VOB_29") (pintype "passive"))
      (node (ref "D34") (pin "30") (pinfunction "VDD_30") (pintype "passive"))
      (node (ref "D34") (pin "38") (pinfunction "VOB_38") (pintype "passive"))
      (node (ref "D34") (pin "39") (pinfunction "VOB_39") (pintype "passive"))
      (node (ref "D34") (pin "EP5") (pinfunction "EP5_EP5") (pintype "passive"))
      (node (ref "D34") (pin "EP6") (pinfunction "EP6_EP6") (pintype "passive"))
      (node (ref "R334") (pin "2") (pinfunction "2_2") (pintype "passive"))
      (node (ref "VD47") (pin "1") (pinfunction "C_1") (pintype "passive"))
      (node (ref "VD50") (pin "2") (pinfunction "A_2") (pintype "passive"))
    )
    (net (code "62") (name "SH") (class "Default")
      (node (ref "C459") (pin "2") (pinfunction "2_2") (pintype "passive"))
      (node (ref "C460") (pin "2") (pinfunction "2_2") (pintype "passive"))
      (node (ref "C467") (pin "2") (pinfunction "2_2") (pintype "passive"))
      (node (ref "C468") (pin "1") (pinfunction "1_1") (pintype "passive"))
      (node (ref "C469") (pin "1") (pinfunction "1_1") (pintype "passive"))
      (node (ref "C475") (pin "2") (pinfunction "2_2") (pintype "passive"))
      (node (ref "C476") (pin "2") (pinfunction "2_2") (pintype "passive"))
      (node (ref "R336") (pin "1") (pinfunction "1_1") (pintype "passive"))
      (node (ref "R341") (pin "2") (pinfunction "2_2") (pintype "passive"))
      (node (ref "R350") (pin "2") (pinfunction "2_2") (pintype "passive"))
    )
    (net (code "63") (name "VCC_3V3_S3") (class "Default")
      (node (ref "R345") (pin "1") (pinfunction "1_1") (pintype "passive"))
    )
  )
)
